# mac-protoshield.net
KiCad netlist of a schematic drawn in EAGLE
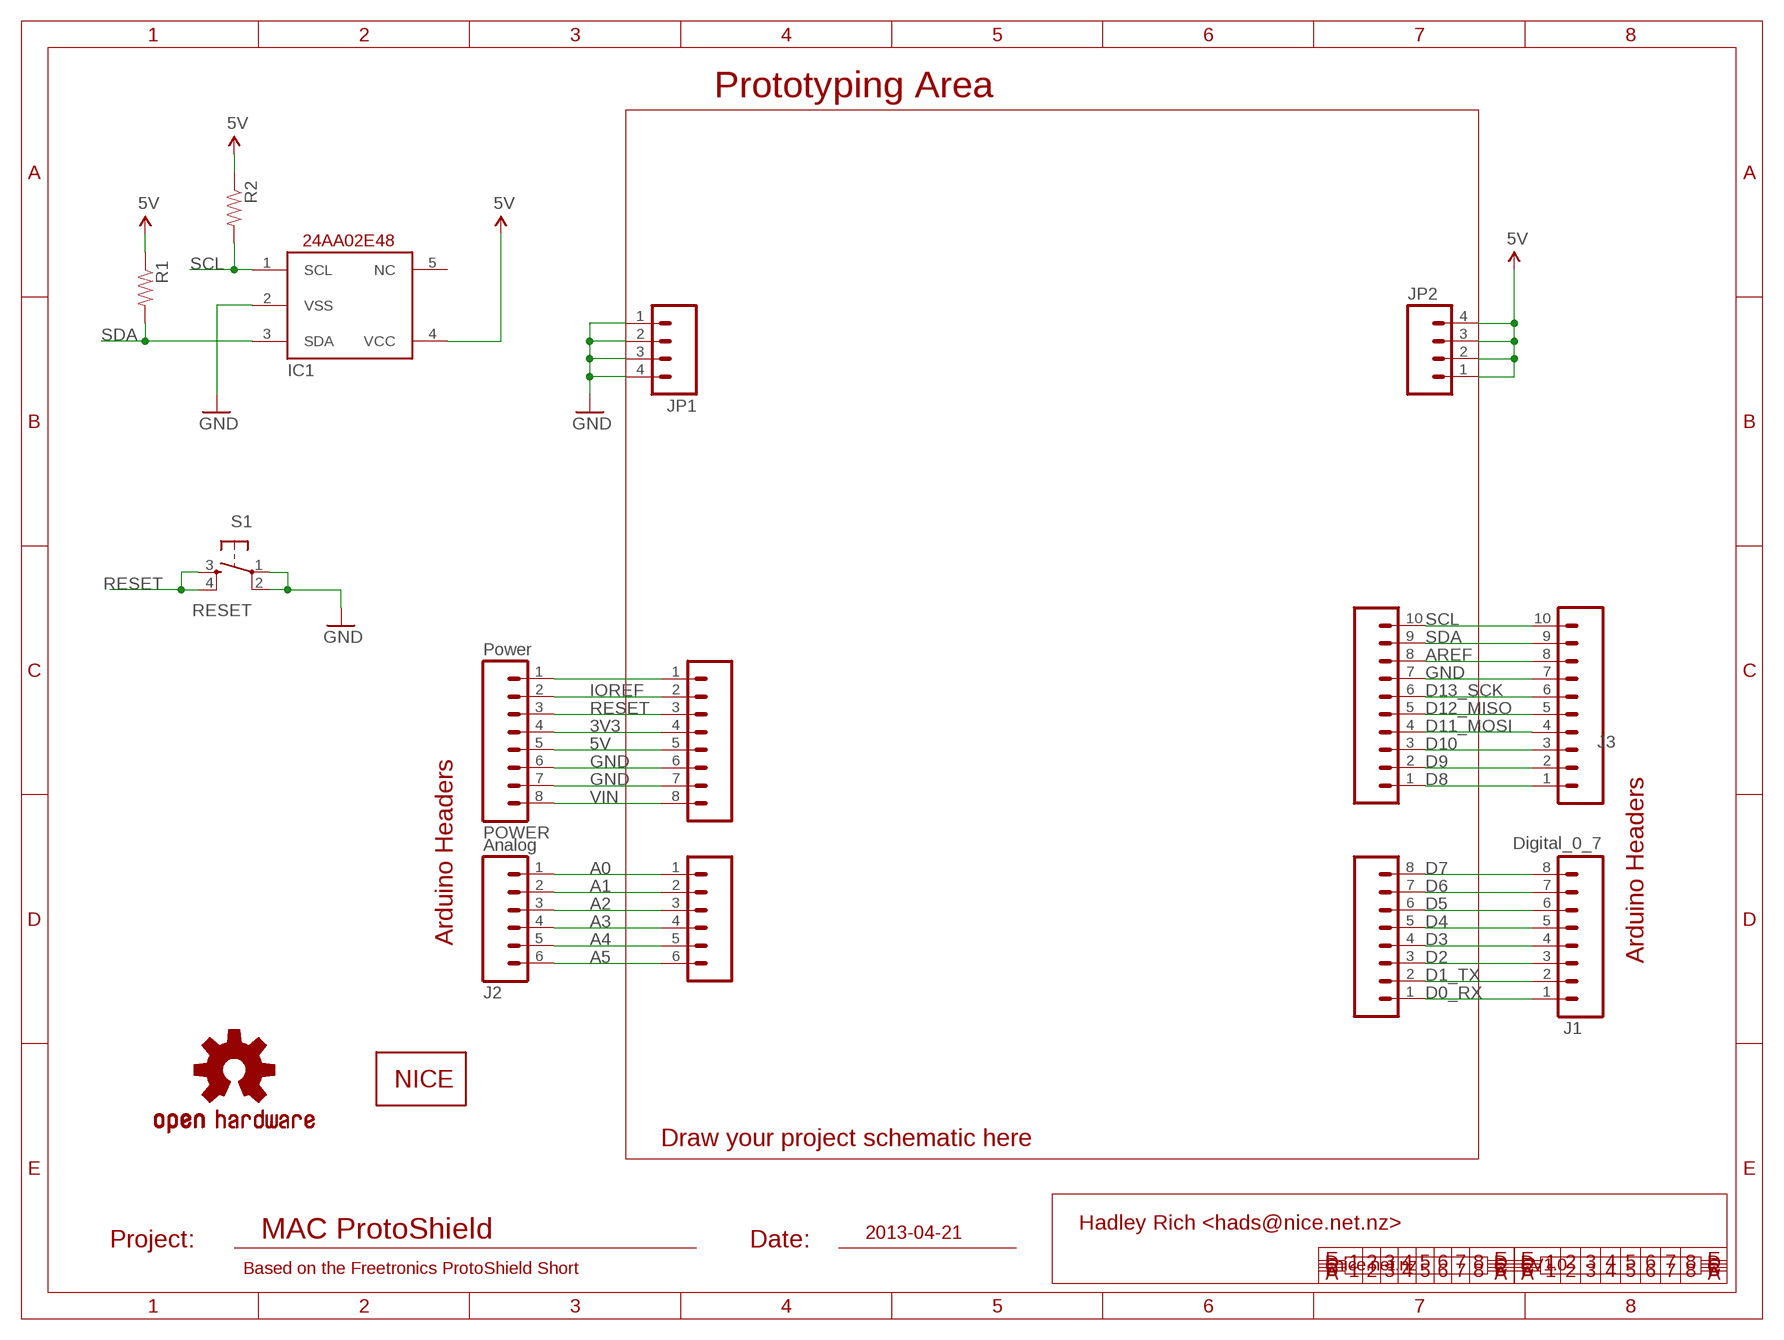
[diagram p0: schematic, sheet 1]

(export (version "E")
  (design (tool "Eeschema 10.0.6"))
  (components
    (comp (ref "IC1")
      (value "24AA-2E48")
      (footprint "eagle-import:SOT23-5")
      (libsource (lib "eagle-import") (part "24AA-2E48"))
    )
    (comp (ref "J1")
      (value "Digital_0_7")
      (footprint "eagle-import:1X08")
      (libsource (lib "eagle-import") (part "M081X08"))
    )
    (comp (ref "J2")
      (value "Analog")
      (footprint "eagle-import:1X06")
      (libsource (lib "eagle-import") (part "M06SIP"))
    )
    (comp (ref "J3")
      (value "Digital_8_13")
      (footprint "eagle-import:1X10")
      (libsource (lib "eagle-import") (part "M10{dblquote}"))
    )
    (comp (ref "JP1")
      (value "M04PTH")
      (footprint "eagle-import:1X04")
      (libsource (lib "eagle-import") (part "M04PTH"))
    )
    (comp (ref "JP2")
      (value "M04PTH")
      (footprint "eagle-import:1X04")
      (libsource (lib "eagle-import") (part "M04PTH"))
    )
    (comp (ref "LOGO1")
      (value "OSHW-LOGOS")
      (footprint "eagle-import:OSHW-LOGO-S")
      (libsource (lib "eagle-import") (part "OSHW-LOGOS"))
    )
    (comp (ref "POWER")
      (value "Power")
      (footprint "eagle-import:1X08")
      (libsource (lib "eagle-import") (part "M081X08"))
    )
    (comp (ref "R1")
      (value "RESISTOR0805-RES")
      (footprint "eagle-import:0805")
      (libsource (lib "eagle-import") (part "RESISTOR0805-RES"))
    )
    (comp (ref "R2")
      (value "RESISTOR0805-RES")
      (footprint "eagle-import:0805")
      (libsource (lib "eagle-import") (part "RESISTOR0805-RES"))
    )
    (comp (ref "S1")
      (value "RESET")
      (footprint "eagle-import:TACTILE-PTH")
      (libsource (lib "eagle-import") (part "TAC_SWITCHPTH"))
    )
    (comp (ref "SL1")
      (value "Digital_0_7")
      (footprint "eagle-import:1X08")
      (libsource (lib "eagle-import") (part "M081X08"))
    )
    (comp (ref "SL2")
      (value "Analog")
      (footprint "eagle-import:1X06")
      (libsource (lib "eagle-import") (part "M06SIP"))
    )
    (comp (ref "SL3")
      (value "Digital_8_13")
      (footprint "eagle-import:1X10")
      (libsource (lib "eagle-import") (part "M10{dblquote}"))
    )
    (comp (ref "SLP")
      (value "Power")
      (footprint "eagle-import:1X08")
      (libsource (lib "eagle-import") (part "M081X08"))
    )
    (comp (ref "U$5")
      (value "NICE-LOGO04")
      (footprint "eagle-import:NICE-LOGO-04")
      (libsource (lib "eagle-import") (part "NICE-LOGO04"))
    )
  )
  (nets
    (net (code "1") (name "/3V3") (class "Default")
      (node (ref "POWER") (pin "4") (pinfunction "4_4") (pintype "passive"))
      (node (ref "SLP") (pin "4") (pinfunction "4_4") (pintype "passive"))
    )
    (net (code "2") (name "/A0") (class "Default")
      (node (ref "J2") (pin "1") (pinfunction "1_1") (pintype "passive"))
      (node (ref "SL2") (pin "1") (pinfunction "1_1") (pintype "passive"))
    )
    (net (code "3") (name "/A1") (class "Default")
      (node (ref "J2") (pin "2") (pinfunction "2_2") (pintype "passive"))
      (node (ref "SL2") (pin "2") (pinfunction "2_2") (pintype "passive"))
    )
    (net (code "4") (name "/A2") (class "Default")
      (node (ref "J2") (pin "3") (pinfunction "3_3") (pintype "passive"))
      (node (ref "SL2") (pin "3") (pinfunction "3_3") (pintype "passive"))
    )
    (net (code "5") (name "/A3") (class "Default")
      (node (ref "J2") (pin "4") (pinfunction "4_4") (pintype "passive"))
      (node (ref "SL2") (pin "4") (pinfunction "4_4") (pintype "passive"))
    )
    (net (code "6") (name "/A4") (class "Default")
      (node (ref "J2") (pin "5") (pinfunction "5_5") (pintype "passive"))
      (node (ref "SL2") (pin "5") (pinfunction "5_5") (pintype "passive"))
    )
    (net (code "7") (name "/A5") (class "Default")
      (node (ref "J2") (pin "6") (pinfunction "6_6") (pintype "passive"))
      (node (ref "SL2") (pin "6") (pinfunction "6_6") (pintype "passive"))
    )
    (net (code "8") (name "/AREF") (class "Default")
      (node (ref "J3") (pin "8") (pinfunction "8_8") (pintype "passive"))
      (node (ref "SL3") (pin "8") (pinfunction "8_8") (pintype "passive"))
    )
    (net (code "9") (name "/D0_RX") (class "Default")
      (node (ref "J1") (pin "1") (pinfunction "1_1") (pintype "passive"))
      (node (ref "SL1") (pin "1") (pinfunction "1_1") (pintype "passive"))
    )
    (net (code "10") (name "/D1_TX") (class "Default")
      (node (ref "J1") (pin "2") (pinfunction "2_2") (pintype "passive"))
      (node (ref "SL1") (pin "2") (pinfunction "2_2") (pintype "passive"))
    )
    (net (code "11") (name "/D2") (class "Default")
      (node (ref "J1") (pin "3") (pinfunction "3_3") (pintype "passive"))
      (node (ref "SL1") (pin "3") (pinfunction "3_3") (pintype "passive"))
    )
    (net (code "12") (name "/D3") (class "Default")
      (node (ref "J1") (pin "4") (pinfunction "4_4") (pintype "passive"))
      (node (ref "SL1") (pin "4") (pinfunction "4_4") (pintype "passive"))
    )
    (net (code "13") (name "/D4") (class "Default")
      (node (ref "J1") (pin "5") (pinfunction "5_5") (pintype "passive"))
      (node (ref "SL1") (pin "5") (pinfunction "5_5") (pintype "passive"))
    )
    (net (code "14") (name "/D5") (class "Default")
      (node (ref "J1") (pin "6") (pinfunction "6_6") (pintype "passive"))
      (node (ref "SL1") (pin "6") (pinfunction "6_6") (pintype "passive"))
    )
    (net (code "15") (name "/D6") (class "Default")
      (node (ref "J1") (pin "7") (pinfunction "7_7") (pintype "passive"))
      (node (ref "SL1") (pin "7") (pinfunction "7_7") (pintype "passive"))
    )
    (net (code "16") (name "/D7") (class "Default")
      (node (ref "J1") (pin "8") (pinfunction "8_8") (pintype "passive"))
      (node (ref "SL1") (pin "8") (pinfunction "8_8") (pintype "passive"))
    )
    (net (code "17") (name "/D8") (class "Default")
      (node (ref "J3") (pin "1") (pinfunction "1_1") (pintype "passive"))
      (node (ref "SL3") (pin "1") (pinfunction "1_1") (pintype "passive"))
    )
    (net (code "18") (name "/D9") (class "Default")
      (node (ref "J3") (pin "2") (pinfunction "2_2") (pintype "passive"))
      (node (ref "SL3") (pin "2") (pinfunction "2_2") (pintype "passive"))
    )
    (net (code "19") (name "/D10") (class "Default")
      (node (ref "J3") (pin "3") (pinfunction "3_3") (pintype "passive"))
      (node (ref "SL3") (pin "3") (pinfunction "3_3") (pintype "passive"))
    )
    (net (code "20") (name "/D11_MOSI") (class "Default")
      (node (ref "J3") (pin "4") (pinfunction "4_4") (pintype "passive"))
      (node (ref "SL3") (pin "4") (pinfunction "4_4") (pintype "passive"))
    )
    (net (code "21") (name "/D12_MISO") (class "Default")
      (node (ref "J3") (pin "5") (pinfunction "5_5") (pintype "passive"))
      (node (ref "SL3") (pin "5") (pinfunction "5_5") (pintype "passive"))
    )
    (net (code "22") (name "/D13_SCK") (class "Default")
      (node (ref "J3") (pin "6") (pinfunction "6_6") (pintype "passive"))
      (node (ref "SL3") (pin "6") (pinfunction "6_6") (pintype "passive"))
    )
    (net (code "23") (name "/IOREF") (class "Default")
      (node (ref "POWER") (pin "2") (pinfunction "2_2") (pintype "passive"))
      (node (ref "SLP") (pin "2") (pinfunction "2_2") (pintype "passive"))
    )
    (net (code "24") (name "/RESET") (class "Default")
      (node (ref "POWER") (pin "3") (pinfunction "3_3") (pintype "passive"))
      (node (ref "S1") (pin "3") (pinfunction "3_3") (pintype "passive"))
      (node (ref "S1") (pin "4") (pinfunction "4_4") (pintype "passive"))
      (node (ref "SLP") (pin "3") (pinfunction "3_3") (pintype "passive"))
    )
    (net (code "25") (name "/SCL") (class "Default")
      (node (ref "IC1") (pin "1") (pinfunction "SCL_1") (pintype "input"))
      (node (ref "J3") (pin "10") (pinfunction "10_10") (pintype "passive"))
      (node (ref "R2") (pin "2") (pinfunction "2_2") (pintype "passive"))
      (node (ref "SL3") (pin "10") (pinfunction "10_10") (pintype "passive"))
    )
    (net (code "26") (name "/SDA") (class "Default")
      (node (ref "IC1") (pin "3") (pinfunction "SDA_3") (pintype "bidirectional"))
      (node (ref "J3") (pin "9") (pinfunction "9_9") (pintype "passive"))
      (node (ref "R1") (pin "2") (pinfunction "2_2") (pintype "passive"))
      (node (ref "SL3") (pin "9") (pinfunction "9_9") (pintype "passive"))
    )
    (net (code "27") (name "/VIN") (class "Default")
      (node (ref "POWER") (pin "8") (pinfunction "8_8") (pintype "passive"))
      (node (ref "SLP") (pin "8") (pinfunction "8_8") (pintype "passive"))
    )
    (net (code "28") (name "5V") (class "Default")
      (node (ref "IC1") (pin "4") (pinfunction "VCC_4") (pintype "power_in"))
      (node (ref "JP2") (pin "1") (pinfunction "1_1") (pintype "passive"))
      (node (ref "JP2") (pin "2") (pinfunction "2_2") (pintype "passive"))
      (node (ref "JP2") (pin "3") (pinfunction "3_3") (pintype "passive"))
      (node (ref "JP2") (pin "4") (pinfunction "4_4") (pintype "passive"))
      (node (ref "POWER") (pin "5") (pinfunction "5_5") (pintype "passive"))
      (node (ref "R1") (pin "1") (pinfunction "1_1") (pintype "passive"))
      (node (ref "R2") (pin "1") (pinfunction "1_1") (pintype "passive"))
      (node (ref "SLP") (pin "5") (pinfunction "5_5") (pintype "passive"))
    )
    (net (code "29") (name "GND") (class "Default")
      (node (ref "IC1") (pin "2") (pinfunction "VSS_2") (pintype "power_in"))
      (node (ref "J3") (pin "7") (pinfunction "7_7") (pintype "passive"))
      (node (ref "JP1") (pin "1") (pinfunction "1_1") (pintype "passive"))
      (node (ref "JP1") (pin "2") (pinfunction "2_2") (pintype "passive"))
      (node (ref "JP1") (pin "3") (pinfunction "3_3") (pintype "passive"))
      (node (ref "JP1") (pin "4") (pinfunction "4_4") (pintype "passive"))
      (node (ref "POWER") (pin "6") (pinfunction "6_6") (pintype "passive"))
      (node (ref "POWER") (pin "7") (pinfunction "7_7") (pintype "passive"))
      (node (ref "S1") (pin "1") (pinfunction "1_1") (pintype "passive"))
      (node (ref "S1") (pin "2") (pinfunction "2_2") (pintype "passive"))
      (node (ref "SL3") (pin "7") (pinfunction "7_7") (pintype "passive"))
      (node (ref "SLP") (pin "6") (pinfunction "6_6") (pintype "passive"))
      (node (ref "SLP") (pin "7") (pinfunction "7_7") (pintype "passive"))
    )
    (net (code "30") (name "Net-(POWER-Pad1)") (class "Default")
      (node (ref "POWER") (pin "1") (pinfunction "1_1") (pintype "passive"))
      (node (ref "SLP") (pin "1") (pinfunction "1_1") (pintype "passive"))
    )
    (net (code "31") (name "unconnected-(IC1-NC-Pad5)") (class "Default")
      (node (ref "IC1") (pin "5") (pinfunction "NC_5") (pintype "input"))
    )
  )
)
